# zikcart-atc256-001.net
KiCad netlist of a schematic drawn in EAGLE
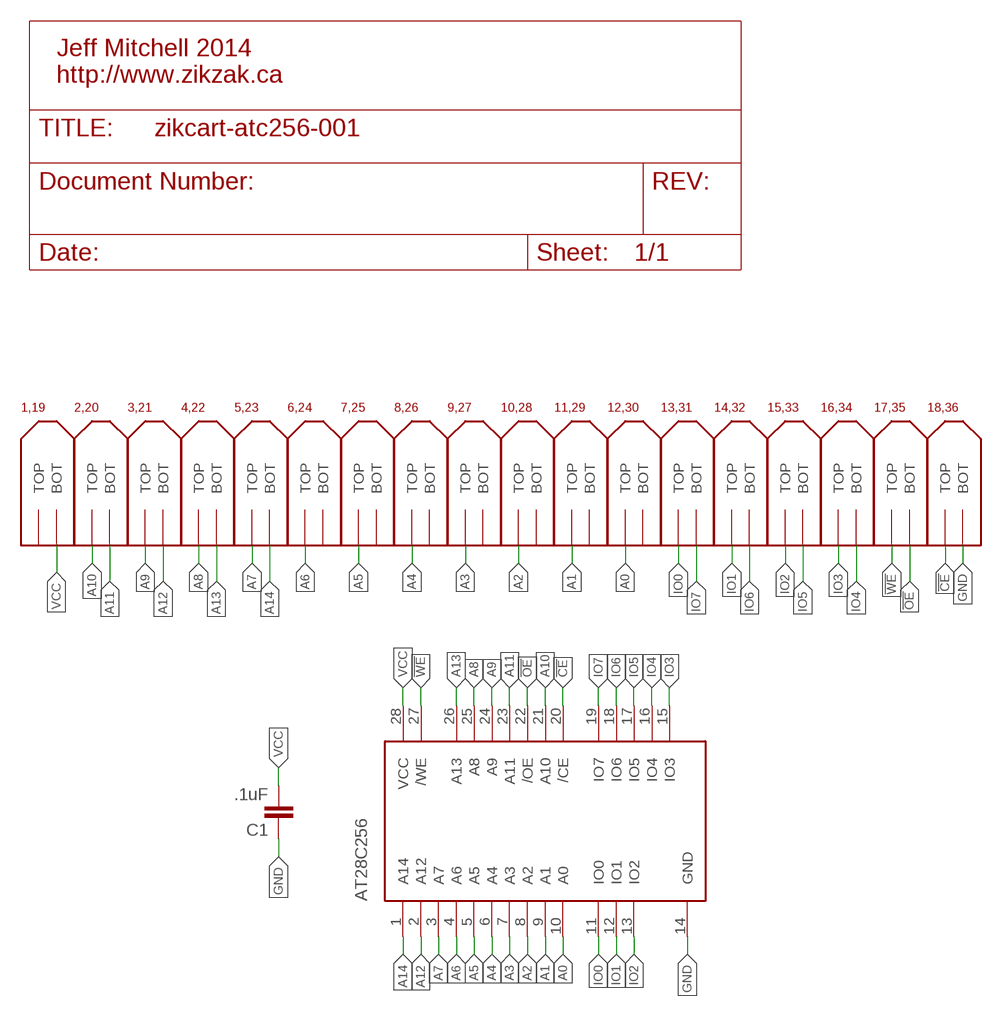
[diagram p0: schematic, sheet 1]

(export (version "E")
  (design (tool "Eeschema 10.0.6"))
  (components
    (comp (ref "1,19")
      (value "ZIKZAKFINGERPAIR2X18")
      (footprint "eagle-import:ZIKZAKFINGERPAIR2X18")
      (libsource (lib "eagle-import") (part "ZIKZAKFINGERPAIR2X18"))
    )
    (comp (ref "2,20")
      (value "ZIKZAKFINGERPAIR2X18")
      (footprint "eagle-import:ZIKZAKFINGERPAIR2X18")
      (libsource (lib "eagle-import") (part "ZIKZAKFINGERPAIR2X18"))
    )
    (comp (ref "3,21")
      (value "ZIKZAKFINGERPAIR2X18")
      (footprint "eagle-import:ZIKZAKFINGERPAIR2X18")
      (libsource (lib "eagle-import") (part "ZIKZAKFINGERPAIR2X18"))
    )
    (comp (ref "4,22")
      (value "ZIKZAKFINGERPAIR2X18")
      (footprint "eagle-import:ZIKZAKFINGERPAIR2X18")
      (libsource (lib "eagle-import") (part "ZIKZAKFINGERPAIR2X18"))
    )
    (comp (ref "5,23")
      (value "ZIKZAKFINGERPAIR2X18")
      (footprint "eagle-import:ZIKZAKFINGERPAIR2X18")
      (libsource (lib "eagle-import") (part "ZIKZAKFINGERPAIR2X18"))
    )
    (comp (ref "6,24")
      (value "ZIKZAKFINGERPAIR2X18")
      (footprint "eagle-import:ZIKZAKFINGERPAIR2X18")
      (libsource (lib "eagle-import") (part "ZIKZAKFINGERPAIR2X18"))
    )
    (comp (ref "7,25")
      (value "ZIKZAKFINGERPAIR2X18")
      (footprint "eagle-import:ZIKZAKFINGERPAIR2X18")
      (libsource (lib "eagle-import") (part "ZIKZAKFINGERPAIR2X18"))
    )
    (comp (ref "8,26")
      (value "ZIKZAKFINGERPAIR2X18")
      (footprint "eagle-import:ZIKZAKFINGERPAIR2X18")
      (libsource (lib "eagle-import") (part "ZIKZAKFINGERPAIR2X18"))
    )
    (comp (ref "9,27")
      (value "ZIKZAKFINGERPAIR2X18")
      (footprint "eagle-import:ZIKZAKFINGERPAIR2X18")
      (libsource (lib "eagle-import") (part "ZIKZAKFINGERPAIR2X18"))
    )
    (comp (ref "10,28")
      (value "ZIKZAKFINGERPAIR2X18")
      (footprint "eagle-import:ZIKZAKFINGERPAIR2X18")
      (libsource (lib "eagle-import") (part "ZIKZAKFINGERPAIR2X18"))
    )
    (comp (ref "11,29")
      (value "ZIKZAKFINGERPAIR2X18")
      (footprint "eagle-import:ZIKZAKFINGERPAIR2X18")
      (libsource (lib "eagle-import") (part "ZIKZAKFINGERPAIR2X18"))
    )
    (comp (ref "12,30")
      (value "ZIKZAKFINGERPAIR2X18")
      (footprint "eagle-import:ZIKZAKFINGERPAIR2X18")
      (libsource (lib "eagle-import") (part "ZIKZAKFINGERPAIR2X18"))
    )
    (comp (ref "13,31")
      (value "ZIKZAKFINGERPAIR2X18")
      (footprint "eagle-import:ZIKZAKFINGERPAIR2X18")
      (libsource (lib "eagle-import") (part "ZIKZAKFINGERPAIR2X18"))
    )
    (comp (ref "14,32")
      (value "ZIKZAKFINGERPAIR2X18")
      (footprint "eagle-import:ZIKZAKFINGERPAIR2X18")
      (libsource (lib "eagle-import") (part "ZIKZAKFINGERPAIR2X18"))
    )
    (comp (ref "15,33")
      (value "ZIKZAKFINGERPAIR2X18")
      (footprint "eagle-import:ZIKZAKFINGERPAIR2X18")
      (libsource (lib "eagle-import") (part "ZIKZAKFINGERPAIR2X18"))
    )
    (comp (ref "16,34")
      (value "ZIKZAKFINGERPAIR2X18")
      (footprint "eagle-import:ZIKZAKFINGERPAIR2X18")
      (libsource (lib "eagle-import") (part "ZIKZAKFINGERPAIR2X18"))
    )
    (comp (ref "17,35")
      (value "ZIKZAKFINGERPAIR2X18")
      (footprint "eagle-import:ZIKZAKFINGERPAIR2X18")
      (libsource (lib "eagle-import") (part "ZIKZAKFINGERPAIR2X18"))
    )
    (comp (ref "18,36")
      (value "ZIKZAKFINGERPAIR2X18")
      (footprint "eagle-import:ZIKZAKFINGERPAIR2X18")
      (libsource (lib "eagle-import") (part "ZIKZAKFINGERPAIR2X18"))
    )
    (comp (ref "AT28C256")
      (value "AT28C256")
      (footprint "eagle-import:DIL28-6")
      (libsource (lib "eagle-import") (part "AT28C256"))
    )
    (comp (ref "C1")
      (value ".1uF")
      (footprint "eagle-import:C025-030X050")
      (libsource (lib "eagle-import") (part "C-EU025-030X050"))
    )
  )
  (nets
    (net (code "1") (name "/~{CE}") (class "Default")
      (node (ref "18,36") (pin "P$1") (pinfunction "TOP_P$1") (pintype "bidirectional"))
      (node (ref "AT28C256") (pin "20") (pinfunction "/CE_20") (pintype "input"))
    )
    (net (code "2") (name "/~{OE}") (class "Default")
      (node (ref "17,35") (pin "P$2") (pinfunction "BOT_P$2") (pintype "bidirectional"))
      (node (ref "AT28C256") (pin "22") (pinfunction "/OE_22") (pintype "input"))
    )
    (net (code "3") (name "/~{WE}") (class "Default")
      (node (ref "17,35") (pin "P$1") (pinfunction "TOP_P$1") (pintype "bidirectional"))
      (node (ref "AT28C256") (pin "27") (pinfunction "/WE_27") (pintype "input"))
    )
    (net (code "4") (name "A0") (class "Default")
      (node (ref "12,30") (pin "P$1") (pinfunction "TOP_P$1") (pintype "bidirectional"))
      (node (ref "AT28C256") (pin "10") (pinfunction "A0_10") (pintype "input"))
    )
    (net (code "5") (name "A1") (class "Default")
      (node (ref "11,29") (pin "P$1") (pinfunction "TOP_P$1") (pintype "bidirectional"))
      (node (ref "AT28C256") (pin "9") (pinfunction "A1_9") (pintype "input"))
    )
    (net (code "6") (name "A2") (class "Default")
      (node (ref "10,28") (pin "P$1") (pinfunction "TOP_P$1") (pintype "bidirectional"))
      (node (ref "AT28C256") (pin "8") (pinfunction "A2_8") (pintype "input"))
    )
    (net (code "7") (name "A3") (class "Default")
      (node (ref "9,27") (pin "P$1") (pinfunction "TOP_P$1") (pintype "bidirectional"))
      (node (ref "AT28C256") (pin "7") (pinfunction "A3_7") (pintype "input"))
    )
    (net (code "8") (name "A4") (class "Default")
      (node (ref "8,26") (pin "P$1") (pinfunction "TOP_P$1") (pintype "bidirectional"))
      (node (ref "AT28C256") (pin "6") (pinfunction "A4_6") (pintype "input"))
    )
    (net (code "9") (name "A5") (class "Default")
      (node (ref "7,25") (pin "P$1") (pinfunction "TOP_P$1") (pintype "bidirectional"))
      (node (ref "AT28C256") (pin "5") (pinfunction "A5_5") (pintype "input"))
    )
    (net (code "10") (name "A6") (class "Default")
      (node (ref "6,24") (pin "P$1") (pinfunction "TOP_P$1") (pintype "bidirectional"))
      (node (ref "AT28C256") (pin "4") (pinfunction "A6_4") (pintype "input"))
    )
    (net (code "11") (name "A7") (class "Default")
      (node (ref "5,23") (pin "P$1") (pinfunction "TOP_P$1") (pintype "bidirectional"))
      (node (ref "AT28C256") (pin "3") (pinfunction "A7_3") (pintype "input"))
    )
    (net (code "12") (name "A8") (class "Default")
      (node (ref "4,22") (pin "P$1") (pinfunction "TOP_P$1") (pintype "bidirectional"))
      (node (ref "AT28C256") (pin "25") (pinfunction "A8_25") (pintype "input"))
    )
    (net (code "13") (name "A9") (class "Default")
      (node (ref "3,21") (pin "P$1") (pinfunction "TOP_P$1") (pintype "bidirectional"))
      (node (ref "AT28C256") (pin "24") (pinfunction "A9_24") (pintype "input"))
    )
    (net (code "14") (name "A10") (class "Default")
      (node (ref "2,20") (pin "P$1") (pinfunction "TOP_P$1") (pintype "bidirectional"))
      (node (ref "AT28C256") (pin "21") (pinfunction "A10_21") (pintype "input"))
    )
    (net (code "15") (name "A11") (class "Default")
      (node (ref "2,20") (pin "P$2") (pinfunction "BOT_P$2") (pintype "bidirectional"))
      (node (ref "AT28C256") (pin "23") (pinfunction "A11_23") (pintype "input"))
    )
    (net (code "16") (name "A12") (class "Default")
      (node (ref "3,21") (pin "P$2") (pinfunction "BOT_P$2") (pintype "bidirectional"))
      (node (ref "AT28C256") (pin "2") (pinfunction "A12_2") (pintype "input"))
    )
    (net (code "17") (name "A13") (class "Default")
      (node (ref "4,22") (pin "P$2") (pinfunction "BOT_P$2") (pintype "bidirectional"))
      (node (ref "AT28C256") (pin "26") (pinfunction "A13_26") (pintype "input"))
    )
    (net (code "18") (name "A14") (class "Default")
      (node (ref "5,23") (pin "P$2") (pinfunction "BOT_P$2") (pintype "bidirectional"))
      (node (ref "AT28C256") (pin "1") (pinfunction "A14_1") (pintype "input"))
    )
    (net (code "19") (name "GND") (class "Default")
      (node (ref "18,36") (pin "P$2") (pinfunction "BOT_P$2") (pintype "bidirectional"))
      (node (ref "AT28C256") (pin "14") (pinfunction "GND_14") (pintype "power_in"))
      (node (ref "C1") (pin "1") (pinfunction "1_1") (pintype "passive"))
    )
    (net (code "20") (name "IO0") (class "Default")
      (node (ref "13,31") (pin "P$1") (pinfunction "TOP_P$1") (pintype "bidirectional"))
      (node (ref "AT28C256") (pin "11") (pinfunction "IO0_11") (pintype "bidirectional"))
    )
    (net (code "21") (name "IO1") (class "Default")
      (node (ref "14,32") (pin "P$1") (pinfunction "TOP_P$1") (pintype "bidirectional"))
      (node (ref "AT28C256") (pin "12") (pinfunction "IO1_12") (pintype "bidirectional"))
    )
    (net (code "22") (name "IO2") (class "Default")
      (node (ref "15,33") (pin "P$1") (pinfunction "TOP_P$1") (pintype "bidirectional"))
      (node (ref "AT28C256") (pin "13") (pinfunction "IO2_13") (pintype "bidirectional"))
    )
    (net (code "23") (name "IO3") (class "Default")
      (node (ref "16,34") (pin "P$1") (pinfunction "TOP_P$1") (pintype "bidirectional"))
      (node (ref "AT28C256") (pin "15") (pinfunction "IO3_15") (pintype "bidirectional"))
    )
    (net (code "24") (name "IO4") (class "Default")
      (node (ref "16,34") (pin "P$2") (pinfunction "BOT_P$2") (pintype "bidirectional"))
      (node (ref "AT28C256") (pin "16") (pinfunction "IO4_16") (pintype "bidirectional"))
    )
    (net (code "25") (name "IO5") (class "Default")
      (node (ref "15,33") (pin "P$2") (pinfunction "BOT_P$2") (pintype "bidirectional"))
      (node (ref "AT28C256") (pin "17") (pinfunction "IO5_17") (pintype "bidirectional"))
    )
    (net (code "26") (name "IO6") (class "Default")
      (node (ref "14,32") (pin "P$2") (pinfunction "BOT_P$2") (pintype "bidirectional"))
      (node (ref "AT28C256") (pin "18") (pinfunction "IO6_18") (pintype "bidirectional"))
    )
    (net (code "27") (name "IO7") (class "Default")
      (node (ref "13,31") (pin "P$2") (pinfunction "BOT_P$2") (pintype "bidirectional"))
      (node (ref "AT28C256") (pin "19") (pinfunction "IO7_19") (pintype "bidirectional"))
    )
    (net (code "28") (name "VCC") (class "Default")
      (node (ref "1,19") (pin "P$2") (pinfunction "BOT_P$2") (pintype "bidirectional"))
      (node (ref "AT28C256") (pin "28") (pinfunction "VCC_28") (pintype "power_in"))
      (node (ref "C1") (pin "2") (pinfunction "2_2") (pintype "passive"))
    )
    (net (code "29") (name "unconnected-(1,19-TOP-PadP$1)") (class "Default")
      (node (ref "1,19") (pin "P$1") (pinfunction "TOP_P$1") (pintype "bidirectional"))
    )
    (net (code "30") (name "unconnected-(6,24-BOT-PadP$2)") (class "Default")
      (node (ref "6,24") (pin "P$2") (pinfunction "BOT_P$2") (pintype "bidirectional"))
    )
    (net (code "31") (name "unconnected-(7,25-BOT-PadP$2)") (class "Default")
      (node (ref "7,25") (pin "P$2") (pinfunction "BOT_P$2") (pintype "bidirectional"))
    )
    (net (code "32") (name "unconnected-(8,26-BOT-PadP$2)") (class "Default")
      (node (ref "8,26") (pin "P$2") (pinfunction "BOT_P$2") (pintype "bidirectional"))
    )
    (net (code "33") (name "unconnected-(9,27-BOT-PadP$2)") (class "Default")
      (node (ref "9,27") (pin "P$2") (pinfunction "BOT_P$2") (pintype "bidirectional"))
    )
    (net (code "34") (name "unconnected-(10,28-BOT-PadP$2)") (class "Default")
      (node (ref "10,28") (pin "P$2") (pinfunction "BOT_P$2") (pintype "bidirectional"))
    )
    (net (code "35") (name "unconnected-(11,29-BOT-PadP$2)") (class "Default")
      (node (ref "11,29") (pin "P$2") (pinfunction "BOT_P$2") (pintype "bidirectional"))
    )
    (net (code "36") (name "unconnected-(12,30-BOT-PadP$2)") (class "Default")
      (node (ref "12,30") (pin "P$2") (pinfunction "BOT_P$2") (pintype "bidirectional"))
    )
  )
)
